# FPGA_extFLASH.net
KiCad netlist of a schematic drawn in Altium Designer
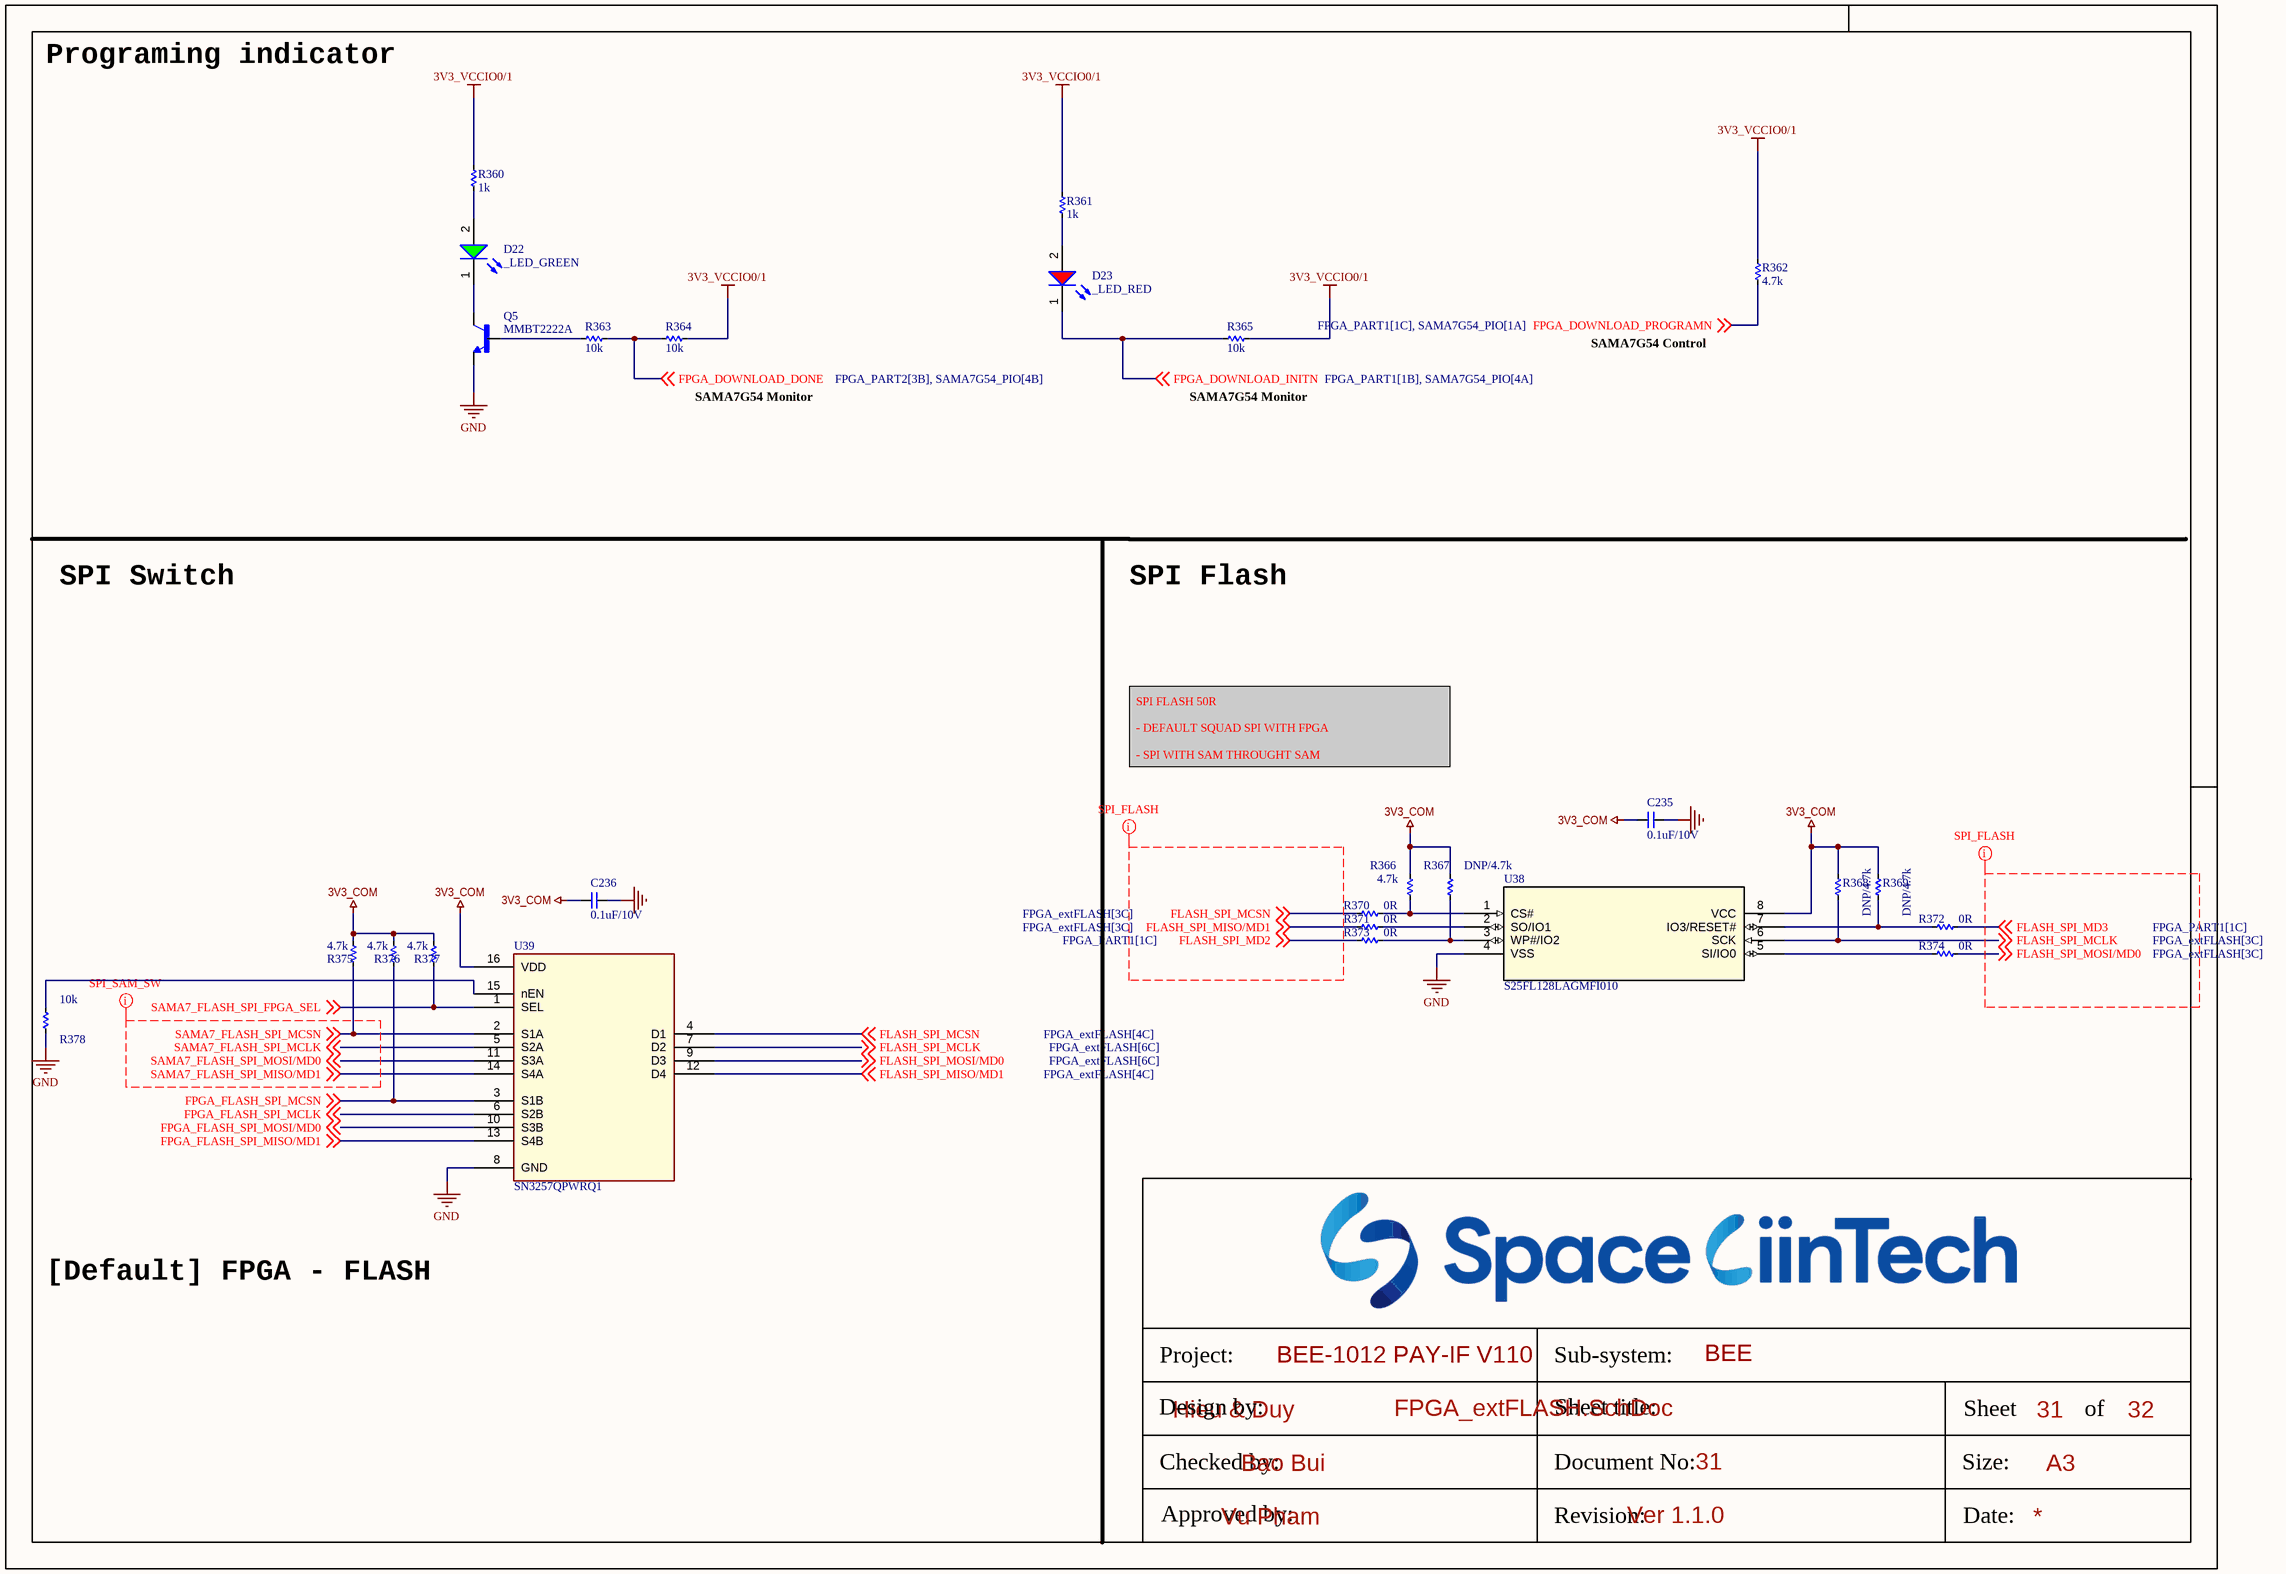
[diagram p0: FPGA_extFLASH.SchDoc]

(export (version "E")
  (design (tool "Eeschema 10.0.6"))
  (components
    (comp (ref "C235")
      (value "0.1uF/10V")
      (footprint "CAP_C_1005X50_L")
      (description "CAP")
      (libsource (lib "LABLIB") (part "_CAP_C_2"))
    )
    (comp (ref "C236")
      (value "0.1uF/10V")
      (footprint "CAP_C_1005X50_L")
      (description "CAP")
      (libsource (lib "LABLIB") (part "_CAP_C_2"))
    )
    (comp (ref "D22")
      (value "_LED_GREEN")
      (footprint "LED_0603")
      (description "LED GREEN CLEAR 0603 SMD")
      (libsource (lib "IFBschelib") (part "LED_GREEN"))
    )
    (comp (ref "D23")
      (value "_LED_RED")
      (footprint "LED_0603")
      (description "LED RED CLEAR 0603 SMD")
      (libsource (lib "IFBschelib") (part "LED_RED"))
    )
    (comp (ref "Q5")
      (value "MMBT2222A")
      (footprint "SOT95P240X120-3N")
      (fields (field (name "MF") "Diotec Semiconductor"))
      (libsource (lib "LABLIB") (part "BJT_NPN_BEC"))
    )
    (comp (ref "R360")
      (value "1k")
      (footprint "RES_C_1005x30_L")
      (description "RES")
      (libsource (lib "LABLIB") (part "_RES_B_2"))
    )
    (comp (ref "R361")
      (value "1k")
      (footprint "RES_C_1005x30_L")
      (description "RES")
      (libsource (lib "LABLIB") (part "_RES_B_2"))
    )
    (comp (ref "R362")
      (value "4.7k")
      (footprint "RES_C_1005x30_L")
      (description "RES")
      (libsource (lib "IFBschelib") (part "_RES_B_2"))
    )
    (comp (ref "R363")
      (value "10k")
      (footprint "RES_C_1005x30_L")
      (description "RES")
      (libsource (lib "LABLIB") (part "_RES_B_2"))
    )
    (comp (ref "R364")
      (value "10k")
      (footprint "RES_C_1005x30_L")
      (description "RES")
      (libsource (lib "LABLIB") (part "_RES_B_2"))
    )
    (comp (ref "R365")
      (value "10k")
      (footprint "RES_C_1005x30_L")
      (description "RES")
      (libsource (lib "LABLIB") (part "_RES_B_2"))
    )
    (comp (ref "R366")
      (value "4.7k")
      (footprint "RES_C_1005x30_L")
      (description "RES")
      (libsource (lib "IFBschelib") (part "_RES_B_2"))
    )
    (comp (ref "R367")
      (value "DNP/4.7k")
      (footprint "RES_C_1005x30_L")
      (description "RES")
      (libsource (lib "IFBschelib") (part "_RES_B_2"))
    )
    (comp (ref "R368")
      (value "DNP/4.7k")
      (footprint "RES_C_1005x30_L")
      (description "RES")
      (libsource (lib "IFBschelib") (part "_RES_B_2"))
    )
    (comp (ref "R369")
      (value "DNP/4.7k")
      (footprint "RES_C_1005x30_L")
      (description "RES")
      (libsource (lib "IFBschelib") (part "_RES_B_2"))
    )
    (comp (ref "R370")
      (value "0R")
      (footprint "RES_C_1005x30_L")
      (description "RES")
      (libsource (lib "LABLIB") (part "_RES_B_2"))
    )
    (comp (ref "R371")
      (value "0R")
      (footprint "RES_C_1005x30_L")
      (description "RES")
      (libsource (lib "LABLIB") (part "_RES_B_2"))
    )
    (comp (ref "R372")
      (value "0R")
      (footprint "RES_C_1005x30_L")
      (description "RES")
      (libsource (lib "LABLIB") (part "_RES_B_2"))
    )
    (comp (ref "R373")
      (value "0R")
      (footprint "RES_C_1005x30_L")
      (description "RES")
      (libsource (lib "LABLIB") (part "_RES_B_2"))
    )
    (comp (ref "R374")
      (value "0R")
      (footprint "RES_C_1005x30_L")
      (description "RES")
      (libsource (lib "LABLIB") (part "_RES_B_2"))
    )
    (comp (ref "R375")
      (value "4.7k")
      (footprint "RES_C_1005x30_L")
      (description "RES")
      (libsource (lib "IFBschelib") (part "_RES_B_2"))
    )
    (comp (ref "R376")
      (value "4.7k")
      (footprint "RES_C_1005x30_L")
      (description "RES")
      (libsource (lib "IFBschelib") (part "_RES_B_2"))
    )
    (comp (ref "R377")
      (value "4.7k")
      (footprint "RES_C_1005x30_L")
      (description "RES")
      (libsource (lib "IFBschelib") (part "_RES_B_2"))
    )
    (comp (ref "R378")
      (value "10k")
      (footprint "RES_C_1005x30_L")
      (description "RES")
      (libsource (lib "LABLIB") (part "_RES_B_2"))
    )
    (comp (ref "U38")
      (value "S25FL128LAGMFI010")
      (footprint "SOIC8_S25FL_CYP")
      (description "Description")
      (fields (field (name "COPYRIGHT") "Copyright (C) 2025 Ultra Librarian. All rights reserved."))
      (libsource (lib "IFBschelib") (part "S25FL128LAGMFI010"))
    )
    (comp (ref "U39")
      (value "SN3257QPWRQ1")
      (footprint "SOIC_PRQ1_TEX")
      (fields (field (name "COPYRIGHT") "Copyright (C) 2025 Ultra Librarian. All rights reserved."))
      (libsource (lib "LABLIB") (part "IC_SW_SPI_SN3257QPWRQ1"))
    )
  )
  (nets
    (net (code "1") (name "3V3_COM") (class "Default")
      (node (ref "C235") (pin "2") (pinfunction "2_2") (pintype "passive"))
      (node (ref "C236") (pin "2") (pinfunction "2_2") (pintype "passive"))
      (node (ref "R366") (pin "2") (pinfunction "2_2") (pintype "passive"))
      (node (ref "R367") (pin "2") (pinfunction "2_2") (pintype "passive"))
      (node (ref "R368") (pin "2") (pinfunction "2_2") (pintype "passive"))
      (node (ref "R369") (pin "2") (pinfunction "2_2") (pintype "passive"))
      (node (ref "R375") (pin "2") (pinfunction "2_2") (pintype "passive"))
      (node (ref "R376") (pin "2") (pinfunction "2_2") (pintype "passive"))
      (node (ref "R377") (pin "2") (pinfunction "2_2") (pintype "passive"))
      (node (ref "U38") (pin "8") (pinfunction "VCC_8") (pintype "power_in"))
      (node (ref "U39") (pin "16") (pinfunction "VDD_16") (pintype "passive"))
    )
    (net (code "2") (name "3V3_VCCIO0{slash}1") (class "Default")
      (node (ref "R360") (pin "2") (pinfunction "2_2") (pintype "passive"))
      (node (ref "R361") (pin "2") (pinfunction "2_2") (pintype "passive"))
      (node (ref "R362") (pin "2") (pinfunction "2_2") (pintype "passive"))
      (node (ref "R364") (pin "1") (pinfunction "1_1") (pintype "passive"))
      (node (ref "R365") (pin "1") (pinfunction "1_1") (pintype "passive"))
    )
    (net (code "3") (name "FLASH_SPI_MCLK") (class "Default")
      (node (ref "R368") (pin "1") (pinfunction "1_1") (pintype "passive"))
      (node (ref "U38") (pin "6") (pinfunction "SCK_6") (pintype "input"))
      (node (ref "U39") (pin "7") (pinfunction "D2_7") (pintype "passive"))
    )
    (net (code "4") (name "FLASH_SPI_MCSN") (class "Default")
      (node (ref "R370") (pin "1") (pinfunction "1_1") (pintype "passive"))
      (node (ref "U39") (pin "4") (pinfunction "D1_4") (pintype "passive"))
    )
    (net (code "5") (name "FLASH_SPI_MD2") (class "Default")
      (node (ref "R373") (pin "1") (pinfunction "1_1") (pintype "passive"))
    )
    (net (code "6") (name "FLASH_SPI_MD3") (class "Default")
      (node (ref "R372") (pin "2") (pinfunction "2_2") (pintype "passive"))
    )
    (net (code "7") (name "FLASH_SPI_MISO{slash}MD1") (class "Default")
      (node (ref "R371") (pin "1") (pinfunction "1_1") (pintype "passive"))
      (node (ref "U39") (pin "12") (pinfunction "D4_12") (pintype "passive"))
    )
    (net (code "8") (name "FLASH_SPI_MOSI{slash}MD0") (class "Default")
      (node (ref "R374") (pin "2") (pinfunction "2_2") (pintype "passive"))
      (node (ref "U39") (pin "9") (pinfunction "D3_9") (pintype "passive"))
    )
    (net (code "9") (name "FPGA_DOWNLOAD_DONE") (class "Default")
      (node (ref "R363") (pin "1") (pinfunction "1_1") (pintype "passive"))
      (node (ref "R364") (pin "2") (pinfunction "2_2") (pintype "passive"))
    )
    (net (code "10") (name "FPGA_DOWNLOAD_INITN") (class "Default")
      (node (ref "D23") (pin "1") (pinfunction "K_1") (pintype "passive"))
      (node (ref "R365") (pin "2") (pinfunction "2_2") (pintype "passive"))
    )
    (net (code "11") (name "FPGA_DOWNLOAD_PROGRAMN") (class "Default")
      (node (ref "R362") (pin "1") (pinfunction "1_1") (pintype "passive"))
    )
    (net (code "12") (name "FPGA_FLASH_SPI_MCLK") (class "Default")
      (node (ref "U39") (pin "6") (pinfunction "S2B_6") (pintype "passive"))
    )
    (net (code "13") (name "FPGA_FLASH_SPI_MCSN") (class "Default")
      (node (ref "R376") (pin "1") (pinfunction "1_1") (pintype "passive"))
      (node (ref "U39") (pin "3") (pinfunction "S1B_3") (pintype "passive"))
    )
    (net (code "14") (name "FPGA_FLASH_SPI_MISO{slash}MD1") (class "Default")
      (node (ref "U39") (pin "13") (pinfunction "S4B_13") (pintype "passive"))
    )
    (net (code "15") (name "FPGA_FLASH_SPI_MOSI{slash}MD0") (class "Default")
      (node (ref "U39") (pin "10") (pinfunction "S3B_10") (pintype "passive"))
    )
    (net (code "16") (name "GND") (class "Default")
      (node (ref "C235") (pin "1") (pinfunction "1_1") (pintype "passive"))
      (node (ref "C236") (pin "1") (pinfunction "1_1") (pintype "passive"))
      (node (ref "Q5") (pin "2") (pinfunction "E_2") (pintype "passive"))
      (node (ref "R378") (pin "1") (pinfunction "1_1") (pintype "passive"))
      (node (ref "U38") (pin "4") (pinfunction "VSS_4") (pintype "power_in"))
      (node (ref "U39") (pin "8") (pinfunction "GND_8") (pintype "passive"))
    )
    (net (code "17") (name "Net-(D22-A)") (class "Default")
      (node (ref "D22") (pin "2") (pinfunction "A_2") (pintype "passive"))
      (node (ref "R360") (pin "1") (pinfunction "1_1") (pintype "passive"))
    )
    (net (code "18") (name "Net-(D22-K)") (class "Default")
      (node (ref "D22") (pin "1") (pinfunction "K_1") (pintype "passive"))
      (node (ref "Q5") (pin "3") (pinfunction "C_3") (pintype "passive"))
    )
    (net (code "19") (name "Net-(D23-A)") (class "Default")
      (node (ref "D23") (pin "2") (pinfunction "A_2") (pintype "passive"))
      (node (ref "R361") (pin "1") (pinfunction "1_1") (pintype "passive"))
    )
    (net (code "20") (name "Net-(Q5-B)") (class "Default")
      (node (ref "Q5") (pin "1") (pinfunction "B_1") (pintype "passive"))
      (node (ref "R363") (pin "2") (pinfunction "2_2") (pintype "passive"))
    )
    (net (code "21") (name "Net-(U38-CS#)") (class "Default")
      (node (ref "R366") (pin "1") (pinfunction "1_1") (pintype "passive"))
      (node (ref "R370") (pin "2") (pinfunction "2_2") (pintype "passive"))
      (node (ref "U38") (pin "1") (pinfunction "CS#_1") (pintype "input"))
    )
    (net (code "22") (name "Net-(U38-IO3{slash}RESET#)") (class "Default")
      (node (ref "R369") (pin "1") (pinfunction "1_1") (pintype "passive"))
      (node (ref "R372") (pin "1") (pinfunction "1_1") (pintype "passive"))
      (node (ref "U38") (pin "7") (pinfunction "IO3/RESET#_7") (pintype "bidirectional"))
    )
    (net (code "23") (name "Net-(U38-SI{slash}IO0)") (class "Default")
      (node (ref "R374") (pin "1") (pinfunction "1_1") (pintype "passive"))
      (node (ref "U38") (pin "5") (pinfunction "SI/IO0_5") (pintype "bidirectional"))
    )
    (net (code "24") (name "Net-(U38-SO{slash}IO1)") (class "Default")
      (node (ref "R371") (pin "2") (pinfunction "2_2") (pintype "passive"))
      (node (ref "U38") (pin "2") (pinfunction "SO/IO1_2") (pintype "bidirectional"))
    )
    (net (code "25") (name "Net-(U38-WP#{slash}IO2)") (class "Default")
      (node (ref "R367") (pin "1") (pinfunction "1_1") (pintype "passive"))
      (node (ref "R373") (pin "2") (pinfunction "2_2") (pintype "passive"))
      (node (ref "U38") (pin "3") (pinfunction "WP#/IO2_3") (pintype "bidirectional"))
    )
    (net (code "26") (name "Net-(U39-nEN)") (class "Default")
      (node (ref "R378") (pin "2") (pinfunction "2_2") (pintype "passive"))
      (node (ref "U39") (pin "15") (pinfunction "nEN_15") (pintype "passive"))
    )
    (net (code "27") (name "SAMA7_FLASH_SPI_FPGA_SEL") (class "Default")
      (node (ref "R377") (pin "1") (pinfunction "1_1") (pintype "passive"))
      (node (ref "U39") (pin "1") (pinfunction "SEL_1") (pintype "passive"))
    )
    (net (code "28") (name "SAMA7_FLASH_SPI_MCLK") (class "Default")
      (node (ref "U39") (pin "5") (pinfunction "S2A_5") (pintype "passive"))
    )
    (net (code "29") (name "SAMA7_FLASH_SPI_MCSN") (class "Default")
      (node (ref "R375") (pin "1") (pinfunction "1_1") (pintype "passive"))
      (node (ref "U39") (pin "2") (pinfunction "S1A_2") (pintype "passive"))
    )
    (net (code "30") (name "SAMA7_FLASH_SPI_MISO{slash}MD1") (class "Default")
      (node (ref "U39") (pin "14") (pinfunction "S4A_14") (pintype "passive"))
    )
    (net (code "31") (name "SAMA7_FLASH_SPI_MOSI{slash}MD0") (class "Default")
      (node (ref "U39") (pin "11") (pinfunction "S3A_11") (pintype "passive"))
    )
  )
)
